# DigitalLabBoard_Traffic.net
KiCad netlist of a schematic drawn in Altium Designer
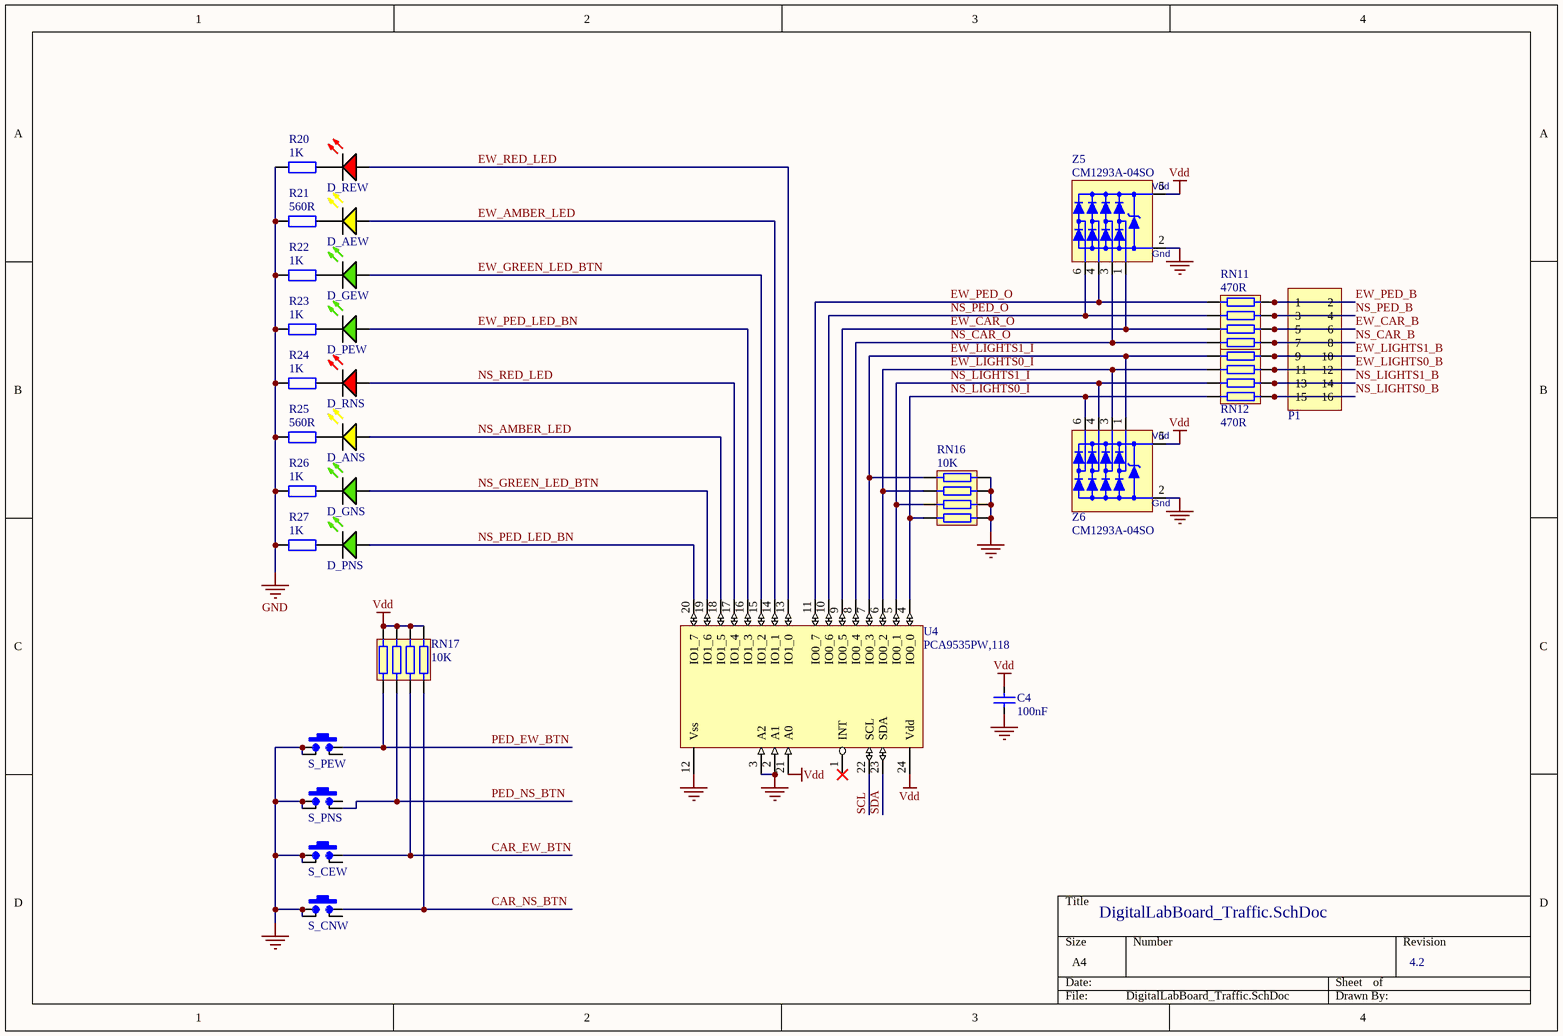
[diagram p0: DigitalLabBoard_Traffic.SchDoc]

(export (version "E")
  (design (tool "Eeschema 10.0.6"))
  (components
    (comp (ref "C4")
      (value "100nF")
      (footprint "CCNP1608-0603")
      (description "Capacitor non-polar SMT 0603")
      (fields
        (field (name "MANUFACTURER") "Generic Components")
        (field (name "PUBLISHER") "Altium Hobart Technology Centre")
      )
      (libsource (lib "MyLibrary") (part "Cap_CCNP_0603"))
    )
    (comp (ref "D_AEW")
      (value "LED Yellow")
      (footprint "LED1608-0603-Yellow")
      (description "LED 0603 Yellow")
      (fields (field (name "MANUFACTURER") "Generic Components") (field (name "PUBLISHER") "Altium Limited"))
      (libsource (lib "MySchLib") (part "LED-0603-Yellow"))
    )
    (comp (ref "D_ANS")
      (value "LED Yellow")
      (footprint "LED1608-0603-Yellow")
      (description "LED 0603 Yellow")
      (fields (field (name "MANUFACTURER") "Generic Components") (field (name "PUBLISHER") "Altium Limited"))
      (libsource (lib "MySchLib") (part "LED-0603-Yellow"))
    )
    (comp (ref "D_GEW")
      (value "LED Green")
      (footprint "LED1608-0603-GREEN")
      (description "LED 0603 Green")
      (fields (field (name "MANUFACTURER") "Generic Components") (field (name "PUBLISHER") "Altium Limited"))
      (libsource (lib "MySchLib") (part "LED-0603-Green"))
    )
    (comp (ref "D_GNS")
      (value "LED Green")
      (footprint "LED1608-0603-GREEN")
      (description "LED 0603 Green")
      (fields (field (name "MANUFACTURER") "Generic Components") (field (name "PUBLISHER") "Altium Limited"))
      (libsource (lib "MySchLib") (part "LED-0603-Green"))
    )
    (comp (ref "D_PEW")
      (value "LED Green")
      (footprint "LED1608-0603-GREEN")
      (description "LED 0603 Green")
      (fields (field (name "MANUFACTURER") "Generic Components") (field (name "PUBLISHER") "Altium Limited"))
      (libsource (lib "MySchLib") (part "LED-0603-Green"))
    )
    (comp (ref "D_PNS")
      (value "LED Green")
      (footprint "LED1608-0603-GREEN")
      (description "LED 0603 Green")
      (fields (field (name "MANUFACTURER") "Generic Components") (field (name "PUBLISHER") "Altium Limited"))
      (libsource (lib "MySchLib") (part "LED-0603-Green"))
    )
    (comp (ref "D_REW")
      (value "LED Red")
      (footprint "LED1608-0603-RED")
      (description "LED 0603 Red")
      (fields (field (name "MANUFACTURER") "Generic Components") (field (name "PUBLISHER") "Altium Limited"))
      (libsource (lib "MySchLib") (part "LED-0603-Red"))
    )
    (comp (ref "D_RNS")
      (value "LED Red")
      (footprint "LED1608-0603-RED")
      (description "LED 0603 Red")
      (fields (field (name "MANUFACTURER") "Generic Components") (field (name "PUBLISHER") "Altium Limited"))
      (libsource (lib "MySchLib") (part "LED-0603-Red"))
    )
    (comp (ref "P1")
      (value "Header 2x8")
      (footprint "HDR2X8S")
      (libsource (lib "MyLibrary") (part "Header 2x8"))
    )
    (comp (ref "R20")
      (value "1K")
      (footprint "CR1608-0603")
      (description "Resistor SMT 0603")
      (fields
        (field (name "MANUFACTURER") "Generic Components")
        (field (name "PUBLISHER") "Altium Hobart Technology Centre")
      )
      (libsource (lib "MyLibrary") (part "Res_CR0603"))
    )
    (comp (ref "R21")
      (value "560R")
      (footprint "CR1608-0603")
      (description "Resistor SMT 0603")
      (fields
        (field (name "MANUFACTURER") "Generic Components")
        (field (name "PUBLISHER") "Altium Hobart Technology Centre")
      )
      (libsource (lib "MyLibrary") (part "Res_CR0603"))
    )
    (comp (ref "R22")
      (value "1K")
      (footprint "CR1608-0603")
      (description "Resistor SMT 0603")
      (fields
        (field (name "MANUFACTURER") "Generic Components")
        (field (name "PUBLISHER") "Altium Hobart Technology Centre")
      )
      (libsource (lib "MyLibrary") (part "Res_CR0603"))
    )
    (comp (ref "R23")
      (value "1K")
      (footprint "CR1608-0603")
      (description "Resistor SMT 0603")
      (fields
        (field (name "MANUFACTURER") "Generic Components")
        (field (name "PUBLISHER") "Altium Hobart Technology Centre")
      )
      (libsource (lib "MyLibrary") (part "Res_CR0603"))
    )
    (comp (ref "R24")
      (value "1K")
      (footprint "CR1608-0603")
      (description "Resistor SMT 0603")
      (fields
        (field (name "MANUFACTURER") "Generic Components")
        (field (name "PUBLISHER") "Altium Hobart Technology Centre")
      )
      (libsource (lib "MyLibrary") (part "Res_CR0603"))
    )
    (comp (ref "R25")
      (value "560R")
      (footprint "CR1608-0603")
      (description "Resistor SMT 0603")
      (fields
        (field (name "MANUFACTURER") "Generic Components")
        (field (name "PUBLISHER") "Altium Hobart Technology Centre")
      )
      (libsource (lib "MyLibrary") (part "Res_CR0603"))
    )
    (comp (ref "R26")
      (value "1K")
      (footprint "CR1608-0603")
      (description "Resistor SMT 0603")
      (fields
        (field (name "MANUFACTURER") "Generic Components")
        (field (name "PUBLISHER") "Altium Hobart Technology Centre")
      )
      (libsource (lib "MyLibrary") (part "Res_CR0603"))
    )
    (comp (ref "R27")
      (value "1K")
      (footprint "CR1608-0603")
      (description "Resistor SMT 0603")
      (fields
        (field (name "MANUFACTURER") "Generic Components")
        (field (name "PUBLISHER") "Altium Hobart Technology Centre")
      )
      (libsource (lib "MyLibrary") (part "Res_CR0603"))
    )
    (comp (ref "RN11")
      (value "470R")
      (footprint "CR1206-0603_X4_N")
      (description "SMT x4 Resistor Array")
      (libsource (lib "MyLibrary") (part "ResistorNetwork_CR0603x4"))
    )
    (comp (ref "RN12")
      (value "470R")
      (footprint "CR1206-0603_X4_N")
      (description "SMT x4 Resistor Array")
      (libsource (lib "MyLibrary") (part "ResistorNetwork_CR0603x4"))
    )
    (comp (ref "RN16")
      (value "10K")
      (footprint "CR1206-0603_X4_N")
      (description "SMT x4 Resistor Array")
      (libsource (lib "MyLibrary") (part "ResistorNetwork_CR0603x4"))
    )
    (comp (ref "RN17")
      (value "10K")
      (footprint "CR1206-0603_X4_N")
      (description "SMT x4 Resistor Array")
      (libsource (lib "") (part "ResistorNetwork_CR0603x4_1"))
    )
    (comp (ref "S_CEW")
      (value "~")
      (footprint "SMD-SW-4_5.1x5.1x2.0_M")
      (description "Tactile Switch SPST 5.10mm X 5.10mm\r\n(1.5mm=C318884)\r\n(2.0mm=C318888)\r\n(3.5mm=C318886)")
      (libsource (lib "MySchLib") (part "SW_PB-TS"))
    )
    (comp (ref "S_CNW")
      (value "~")
      (footprint "SMD-SW-4_5.1x5.1x2.0_M")
      (description "Tactile Switch SPST 5.10mm X 5.10mm\r\n(1.5mm=C318884)\r\n(2.0mm=C318888)\r\n(3.5mm=C318886)")
      (libsource (lib "MySchLib") (part "SW_PB-TS"))
    )
    (comp (ref "S_PEW")
      (value "~")
      (footprint "SMD-SW-4_5.1x5.1x2.0_M")
      (description "Tactile Switch SPST 5.10mm X 5.10mm\r\n(1.5mm=C318884)\r\n(2.0mm=C318888)\r\n(3.5mm=C318886)")
      (libsource (lib "MySchLib") (part "SW_PB-TS"))
    )
    (comp (ref "S_PNS")
      (value "~")
      (footprint "SMD-SW-4_5.1x5.1x2.0_M")
      (description "Tactile Switch SPST 5.10mm X 5.10mm\r\n(1.5mm=C318884)\r\n(2.0mm=C318888)\r\n(3.5mm=C318886)")
      (libsource (lib "MySchLib") (part "SW_PB-TS"))
    )
    (comp (ref "U4")
      (value "PCA9535PW,118")
      (footprint "TSSOP24_N")
      (description "16-bit I2C I/O Expander (TSSOP24)\r\nNO PUPs on I/O pins")
      (libsource (lib "MySchLib") (part "PCA9535PW,118"))
    )
    (comp (ref "Z5")
      (value "CM1293A-04SO")
      (footprint "SOT457_N")
      (description "Ultra low capacitance quadruple rail-to-rail ESD protection")
      (libsource (lib "MyLibrary") (part "CM1293A-04SO"))
    )
    (comp (ref "Z6")
      (value "CM1293A-04SO")
      (footprint "SOT457_N")
      (description "Ultra low capacitance quadruple rail-to-rail ESD protection")
      (libsource (lib "") (part "CM1293A-04SO_1"))
    )
  )
  (nets
    (net (code "1") (name "/CAR_EW_BTN") (class "Default")
      (node (ref "RN17") (pin "6") (pinfunction "6_6") (pintype "passive"))
      (node (ref "S_CEW") (pin "2b") (pinfunction "2b_2b") (pintype "passive"))
    )
    (net (code "2") (name "/CAR_NS_BTN") (class "Default")
      (node (ref "RN17") (pin "5") (pinfunction "5_5") (pintype "passive"))
      (node (ref "S_CNW") (pin "2b") (pinfunction "2b_2b") (pintype "passive"))
    )
    (net (code "3") (name "/EW_AMBER_LED") (class "Default")
      (node (ref "D_AEW") (pin "A") (pinfunction "A_A") (pintype "passive"))
      (node (ref "U4") (pin "14") (pinfunction "IO1_1_14") (pintype "bidirectional"))
    )
    (net (code "4") (name "/EW_CAR_B") (class "Default")
      (node (ref "P1") (pin "5") (pinfunction "5_5") (pintype "passive"))
      (node (ref "P1") (pin "6") (pinfunction "6_6") (pintype "passive"))
      (node (ref "RN11") (pin "7") (pinfunction "7_7") (pintype "passive"))
    )
    (net (code "5") (name "/EW_CAR_O") (class "Default")
      (node (ref "RN11") (pin "2") (pinfunction "2_2") (pintype "passive"))
      (node (ref "U4") (pin "9") (pinfunction "IO0_5_9") (pintype "bidirectional"))
      (node (ref "Z5") (pin "1") (pintype "passive"))
    )
    (net (code "6") (name "/EW_GREEN_LED_BTN") (class "Default")
      (node (ref "D_GEW") (pin "A") (pinfunction "A_A") (pintype "passive"))
      (node (ref "U4") (pin "15") (pinfunction "IO1_2_15") (pintype "bidirectional"))
    )
    (net (code "7") (name "/EW_LIGHTS0_B") (class "Default")
      (node (ref "P1") (pin "11") (pinfunction "11_11") (pintype "passive"))
      (node (ref "P1") (pin "12") (pinfunction "12_12") (pintype "passive"))
      (node (ref "RN12") (pin "6") (pinfunction "6_6") (pintype "passive"))
    )
    (net (code "8") (name "/EW_LIGHTS0_I") (class "Default")
      (node (ref "RN12") (pin "3") (pinfunction "3_3") (pintype "passive"))
      (node (ref "RN16") (pin "3") (pinfunction "3_3") (pintype "passive"))
      (node (ref "U4") (pin "6") (pinfunction "IO0_2_6") (pintype "bidirectional"))
      (node (ref "Z6") (pin "3") (pintype "passive"))
    )
    (net (code "9") (name "/EW_LIGHTS1_B") (class "Default")
      (node (ref "P1") (pin "10") (pinfunction "10_10") (pintype "passive"))
      (node (ref "P1") (pin "9") (pinfunction "9_9") (pintype "passive"))
      (node (ref "RN12") (pin "5") (pinfunction "5_5") (pintype "passive"))
    )
    (net (code "10") (name "/EW_LIGHTS1_I") (class "Default")
      (node (ref "RN12") (pin "4") (pinfunction "4_4") (pintype "passive"))
      (node (ref "RN16") (pin "4") (pinfunction "4_4") (pintype "passive"))
      (node (ref "U4") (pin "7") (pinfunction "IO0_3_7") (pintype "bidirectional"))
      (node (ref "Z6") (pin "1") (pintype "passive"))
    )
    (net (code "11") (name "/EW_PED_B") (class "Default")
      (node (ref "P1") (pin "1") (pinfunction "1_1") (pintype "passive"))
      (node (ref "P1") (pin "2") (pinfunction "2_2") (pintype "passive"))
      (node (ref "RN11") (pin "5") (pinfunction "5_5") (pintype "passive"))
    )
    (net (code "12") (name "/EW_PED_LED_BN") (class "Default")
      (node (ref "D_PEW") (pin "A") (pinfunction "A_A") (pintype "passive"))
      (node (ref "U4") (pin "16") (pinfunction "IO1_3_16") (pintype "bidirectional"))
    )
    (net (code "13") (name "/EW_PED_O") (class "Default")
      (node (ref "RN11") (pin "4") (pinfunction "4_4") (pintype "passive"))
      (node (ref "U4") (pin "11") (pinfunction "IO0_7_11") (pintype "bidirectional"))
      (node (ref "Z5") (pin "4") (pintype "passive"))
    )
    (net (code "14") (name "/EW_RED_LED") (class "Default")
      (node (ref "D_REW") (pin "A") (pinfunction "A_A") (pintype "passive"))
      (node (ref "U4") (pin "13") (pinfunction "IO1_0_13") (pintype "bidirectional"))
    )
    (net (code "15") (name "/NS_AMBER_LED") (class "Default")
      (node (ref "D_ANS") (pin "A") (pinfunction "A_A") (pintype "passive"))
      (node (ref "U4") (pin "18") (pinfunction "IO1_5_18") (pintype "bidirectional"))
    )
    (net (code "16") (name "/NS_CAR_B") (class "Default")
      (node (ref "P1") (pin "7") (pinfunction "7_7") (pintype "passive"))
      (node (ref "P1") (pin "8") (pinfunction "8_8") (pintype "passive"))
      (node (ref "RN11") (pin "8") (pinfunction "8_8") (pintype "passive"))
    )
    (net (code "17") (name "/NS_CAR_O") (class "Default")
      (node (ref "RN11") (pin "1") (pinfunction "1_1") (pintype "passive"))
      (node (ref "U4") (pin "8") (pinfunction "IO0_4_8") (pintype "bidirectional"))
      (node (ref "Z5") (pin "3") (pintype "passive"))
    )
    (net (code "18") (name "/NS_GREEN_LED_BTN") (class "Default")
      (node (ref "D_GNS") (pin "A") (pinfunction "A_A") (pintype "passive"))
      (node (ref "U4") (pin "19") (pinfunction "IO1_6_19") (pintype "bidirectional"))
    )
    (net (code "19") (name "/NS_LIGHTS0_B") (class "Default")
      (node (ref "P1") (pin "15") (pinfunction "15_15") (pintype "passive"))
      (node (ref "P1") (pin "16") (pinfunction "16_16") (pintype "passive"))
      (node (ref "RN12") (pin "8") (pinfunction "8_8") (pintype "passive"))
    )
    (net (code "20") (name "/NS_LIGHTS0_I") (class "Default")
      (node (ref "RN12") (pin "1") (pinfunction "1_1") (pintype "passive"))
      (node (ref "RN16") (pin "1") (pinfunction "1_1") (pintype "passive"))
      (node (ref "U4") (pin "4") (pinfunction "IO0_0_4") (pintype "bidirectional"))
      (node (ref "Z6") (pin "6") (pintype "passive"))
    )
    (net (code "21") (name "/NS_LIGHTS1_B") (class "Default")
      (node (ref "P1") (pin "13") (pinfunction "13_13") (pintype "passive"))
      (node (ref "P1") (pin "14") (pinfunction "14_14") (pintype "passive"))
      (node (ref "RN12") (pin "7") (pinfunction "7_7") (pintype "passive"))
    )
    (net (code "22") (name "/NS_LIGHTS1_I") (class "Default")
      (node (ref "RN12") (pin "2") (pinfunction "2_2") (pintype "passive"))
      (node (ref "RN16") (pin "2") (pinfunction "2_2") (pintype "passive"))
      (node (ref "U4") (pin "5") (pinfunction "IO0_1_5") (pintype "bidirectional"))
      (node (ref "Z6") (pin "4") (pintype "passive"))
    )
    (net (code "23") (name "/NS_PED_B") (class "Default")
      (node (ref "P1") (pin "3") (pinfunction "3_3") (pintype "passive"))
      (node (ref "P1") (pin "4") (pinfunction "4_4") (pintype "passive"))
      (node (ref "RN11") (pin "6") (pinfunction "6_6") (pintype "passive"))
    )
    (net (code "24") (name "/NS_PED_LED_BN") (class "Default")
      (node (ref "D_PNS") (pin "A") (pinfunction "A_A") (pintype "passive"))
      (node (ref "U4") (pin "20") (pinfunction "IO1_7_20") (pintype "bidirectional"))
    )
    (net (code "25") (name "/NS_PED_O") (class "Default")
      (node (ref "RN11") (pin "3") (pinfunction "3_3") (pintype "passive"))
      (node (ref "U4") (pin "10") (pinfunction "IO0_6_10") (pintype "bidirectional"))
      (node (ref "Z5") (pin "6") (pintype "passive"))
    )
    (net (code "26") (name "/NS_RED_LED") (class "Default")
      (node (ref "D_RNS") (pin "A") (pinfunction "A_A") (pintype "passive"))
      (node (ref "U4") (pin "17") (pinfunction "IO1_4_17") (pintype "bidirectional"))
    )
    (net (code "27") (name "/PED_EW_BTN") (class "Default")
      (node (ref "RN17") (pin "8") (pinfunction "8_8") (pintype "passive"))
      (node (ref "S_PEW") (pin "1b") (pinfunction "1b_1b") (pintype "passive"))
    )
    (net (code "28") (name "/PED_NS_BTN") (class "Default")
      (node (ref "RN17") (pin "7") (pinfunction "7_7") (pintype "passive"))
      (node (ref "S_PNS") (pin "2") (pinfunction "2_2") (pintype "passive"))
    )
    (net (code "29") (name "/SCL") (class "Default")
      (node (ref "U4") (pin "22") (pinfunction "SCL_22") (pintype "bidirectional"))
    )
    (net (code "30") (name "/SDA") (class "Default")
      (node (ref "U4") (pin "23") (pinfunction "SDA_23") (pintype "bidirectional"))
    )
    (net (code "31") (name "GND") (class "Default")
      (node (ref "C4") (pin "1") (pinfunction "1_1") (pintype "passive"))
      (node (ref "R20") (pin "1") (pinfunction "1_1") (pintype "passive"))
      (node (ref "R21") (pin "1") (pinfunction "1_1") (pintype "passive"))
      (node (ref "R22") (pin "1") (pinfunction "1_1") (pintype "passive"))
      (node (ref "R23") (pin "1") (pinfunction "1_1") (pintype "passive"))
      (node (ref "R24") (pin "1") (pinfunction "1_1") (pintype "passive"))
      (node (ref "R25") (pin "1") (pinfunction "1_1") (pintype "passive"))
      (node (ref "R26") (pin "1") (pinfunction "1_1") (pintype "passive"))
      (node (ref "R27") (pin "1") (pinfunction "1_1") (pintype "passive"))
      (node (ref "RN16") (pin "5") (pinfunction "5_5") (pintype "passive"))
      (node (ref "RN16") (pin "6") (pinfunction "6_6") (pintype "passive"))
      (node (ref "RN16") (pin "7") (pinfunction "7_7") (pintype "passive"))
      (node (ref "RN16") (pin "8") (pinfunction "8_8") (pintype "passive"))
      (node (ref "S_CEW") (pin "1") (pinfunction "1_1") (pintype "passive"))
      (node (ref "S_CEW") (pin "1b") (pinfunction "1b_1b") (pintype "passive"))
      (node (ref "S_CNW") (pin "1") (pinfunction "1_1") (pintype "passive"))
      (node (ref "S_CNW") (pin "1b") (pinfunction "1b_1b") (pintype "passive"))
      (node (ref "S_PEW") (pin "2") (pinfunction "2_2") (pintype "passive"))
      (node (ref "S_PEW") (pin "2b") (pinfunction "2b_2b") (pintype "passive"))
      (node (ref "S_PNS") (pin "1") (pinfunction "1_1") (pintype "passive"))
      (node (ref "S_PNS") (pin "1b") (pinfunction "1b_1b") (pintype "passive"))
      (node (ref "U4") (pin "12") (pinfunction "Vss_12") (pintype "power_in"))
      (node (ref "U4") (pin "2") (pinfunction "A1_2") (pintype "input"))
      (node (ref "U4") (pin "3") (pinfunction "A2_3") (pintype "input"))
      (node (ref "Z5") (pin "2") (pintype "passive"))
      (node (ref "Z6") (pin "2") (pinfunction "Vn_2") (pintype "passive"))
    )
    (net (code "32") (name "Net-(D_AEW-PadK)") (class "Default")
      (node (ref "D_AEW") (pin "K") (pinfunction "K_K") (pintype "passive"))
      (node (ref "R21") (pin "2") (pinfunction "2_2") (pintype "passive"))
    )
    (net (code "33") (name "Net-(D_ANS-PadK)") (class "Default")
      (node (ref "D_ANS") (pin "K") (pinfunction "K_K") (pintype "passive"))
      (node (ref "R25") (pin "2") (pinfunction "2_2") (pintype "passive"))
    )
    (net (code "34") (name "Net-(D_GEW-PadK)") (class "Default")
      (node (ref "D_GEW") (pin "K") (pinfunction "K_K") (pintype "passive"))
      (node (ref "R22") (pin "2") (pinfunction "2_2") (pintype "passive"))
    )
    (net (code "35") (name "Net-(D_GNS-PadK)") (class "Default")
      (node (ref "D_GNS") (pin "K") (pinfunction "K_K") (pintype "passive"))
      (node (ref "R26") (pin "2") (pinfunction "2_2") (pintype "passive"))
    )
    (net (code "36") (name "Net-(D_PEW-PadK)") (class "Default")
      (node (ref "D_PEW") (pin "K") (pinfunction "K_K") (pintype "passive"))
      (node (ref "R23") (pin "2") (pinfunction "2_2") (pintype "passive"))
    )
    (net (code "37") (name "Net-(D_PNS-PadK)") (class "Default")
      (node (ref "D_PNS") (pin "K") (pinfunction "K_K") (pintype "passive"))
      (node (ref "R27") (pin "2") (pinfunction "2_2") (pintype "passive"))
    )
    (net (code "38") (name "Net-(D_REW-PadK)") (class "Default")
      (node (ref "D_REW") (pin "K") (pinfunction "K_K") (pintype "passive"))
      (node (ref "R20") (pin "2") (pinfunction "2_2") (pintype "passive"))
    )
    (net (code "39") (name "Net-(D_RNS-PadK)") (class "Default")
      (node (ref "D_RNS") (pin "K") (pinfunction "K_K") (pintype "passive"))
      (node (ref "R24") (pin "2") (pinfunction "2_2") (pintype "passive"))
    )
    (net (code "40") (name "Vdd") (class "Default")
      (node (ref "C4") (pin "2") (pinfunction "2_2") (pintype "passive"))
      (node (ref "RN17") (pin "1") (pinfunction "1_1") (pintype "passive"))
      (node (ref "RN17") (pin "2") (pinfunction "2_2") (pintype "passive"))
      (node (ref "RN17") (pin "3") (pinfunction "3_3") (pintype "passive"))
      (node (ref "RN17") (pin "4") (pinfunction "4_4") (pintype "passive"))
      (node (ref "U4") (pin "21") (pinfunction "A0_21") (pintype "input"))
      (node (ref "U4") (pin "24") (pinfunction "Vdd_24") (pintype "power_in"))
      (node (ref "Z5") (pin "5") (pintype "passive"))
      (node (ref "Z6") (pin "5") (pinfunction "Vp_5") (pintype "passive"))
    )
    (net (code "41") (name "unconnected-(S_CEW-Pad2)") (class "Default")
      (node (ref "S_CEW") (pin "2") (pinfunction "2_2") (pintype "passive"))
    )
    (net (code "42") (name "unconnected-(S_CNW-Pad2)") (class "Default")
      (node (ref "S_CNW") (pin "2") (pinfunction "2_2") (pintype "passive"))
    )
    (net (code "43") (name "unconnected-(S_PEW-Pad1)") (class "Default")
      (node (ref "S_PEW") (pin "1") (pinfunction "1_1") (pintype "passive"))
    )
    (net (code "44") (name "unconnected-(S_PNS-Pad2b)") (class "Default")
      (node (ref "S_PNS") (pin "2b") (pinfunction "2b_2b") (pintype "passive"))
    )
    (net (code "45") (name "unconnected-(U4-INT-Pad1)") (class "Default")
      (node (ref "U4") (pin "1") (pinfunction "INT_1") (pintype "open_collector+no_connect"))
    )
  )
)
